# Beacon_V2.net
KiCad netlist of a schematic drawn in Altium Designer
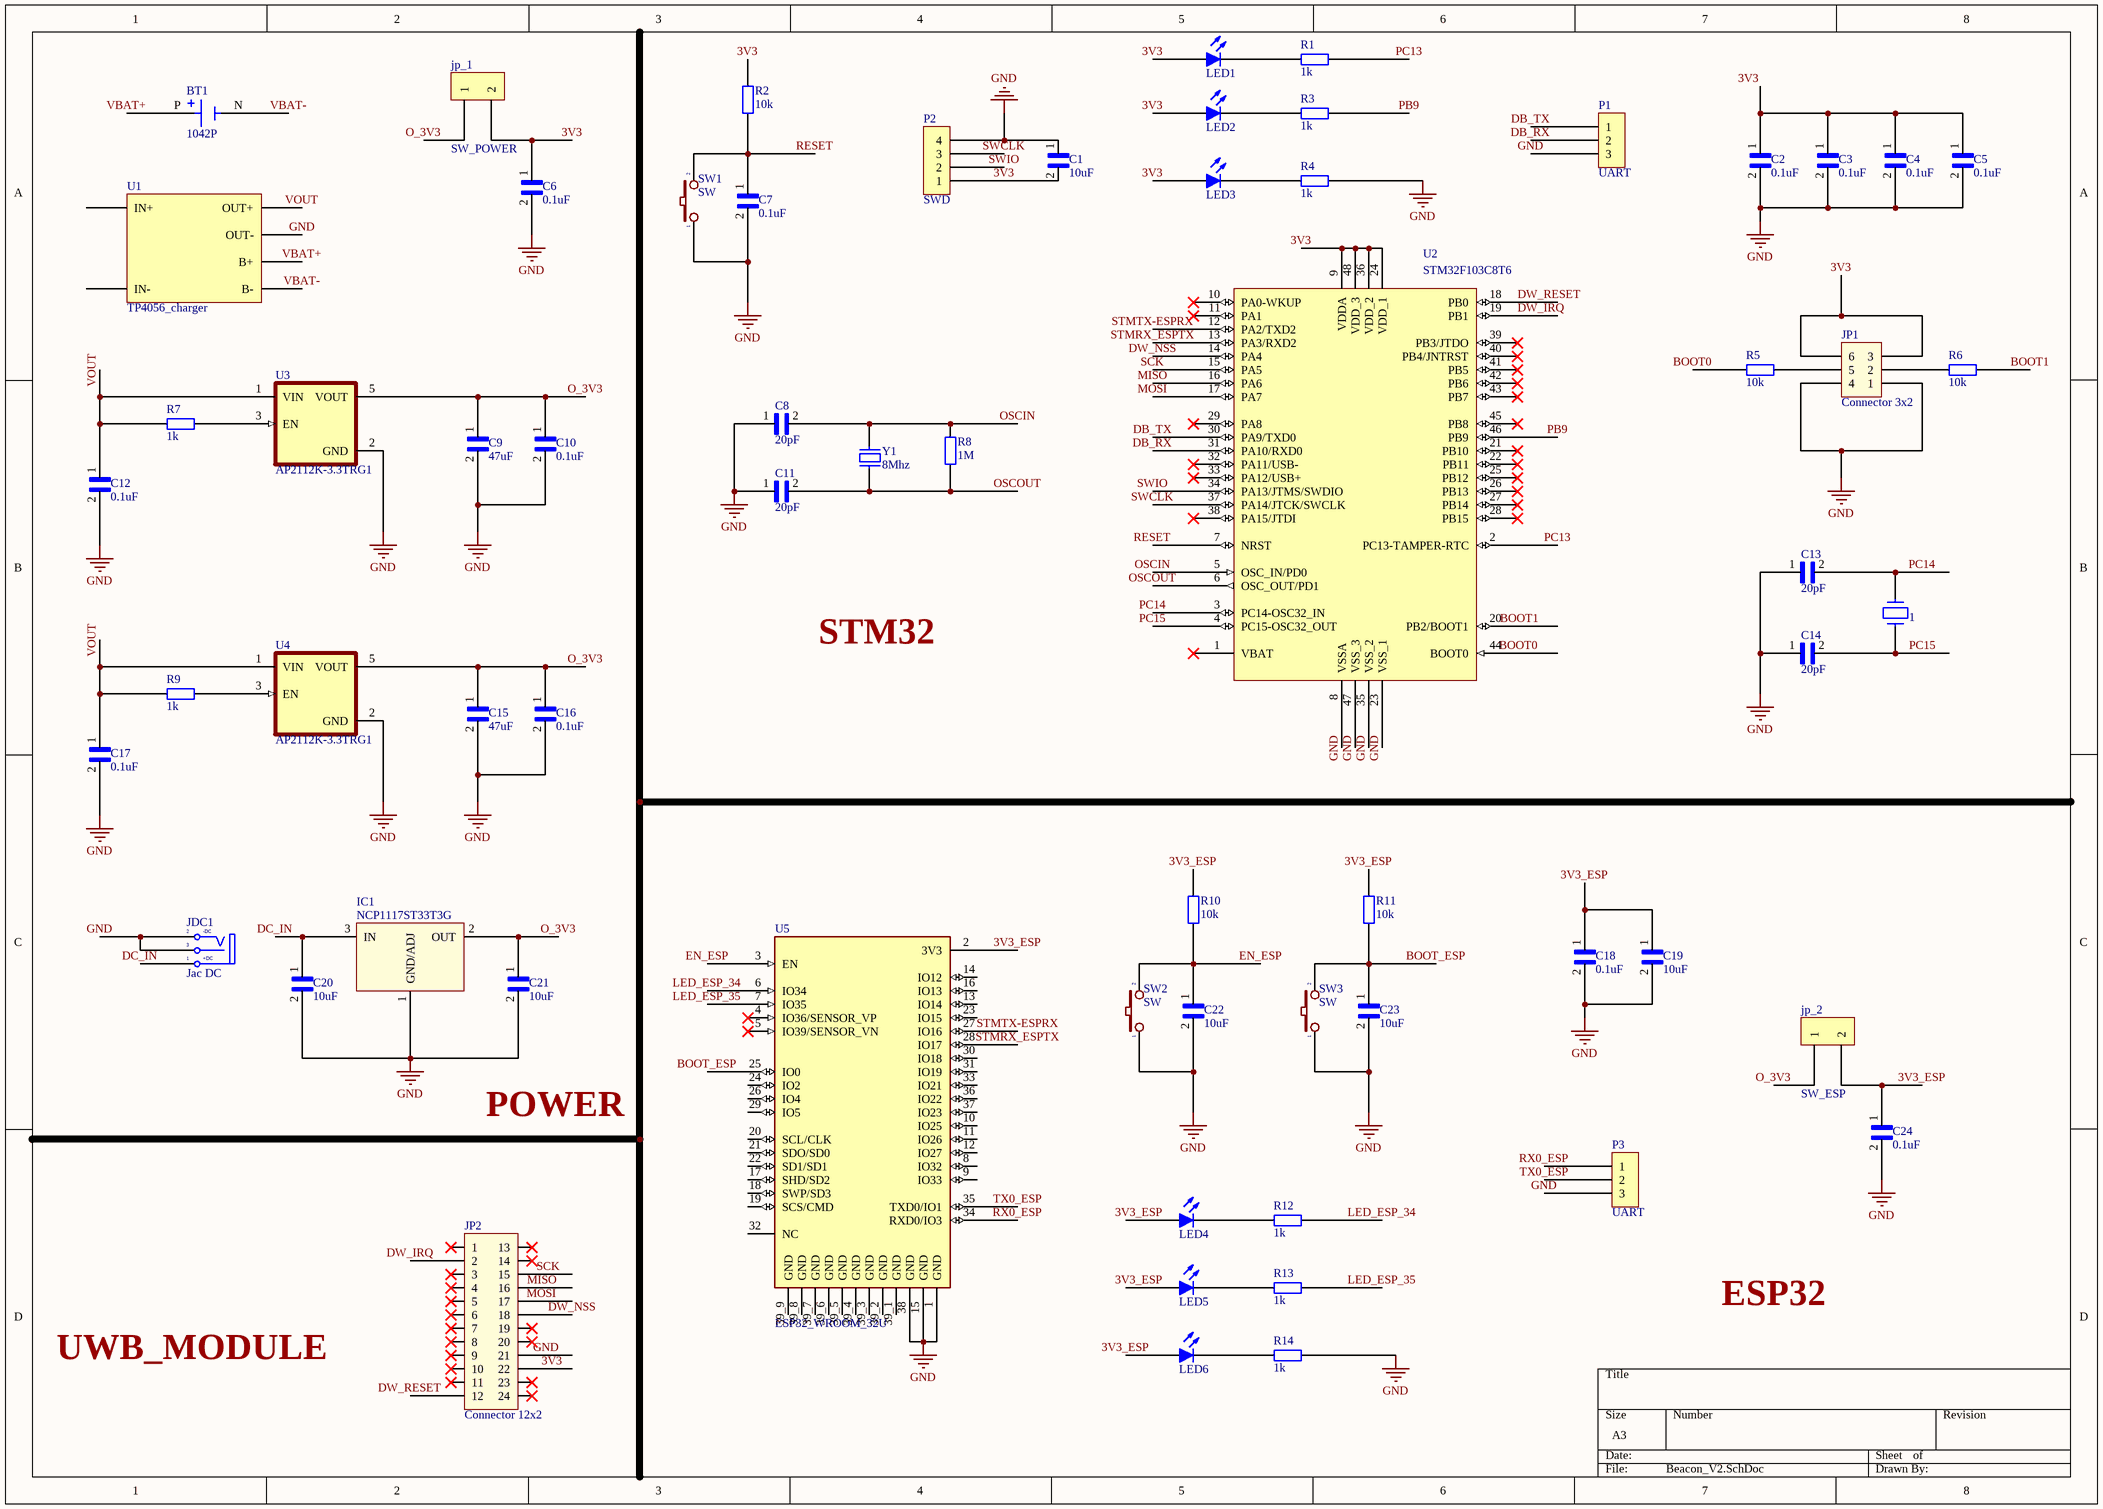
[diagram p0: Beacon_V2.SchDoc]

(export (version "E")
  (design (tool "Eeschema 10.0.6"))
  (components
    (comp (ref "1")
      (value "ABS07")
      (footprint "ABS07")
      (description "SMD Quartz Crystal")
      (fields (field (name "CREATED BY") "Zion Blue") (field (name "PUBLISHER") "Cynetik Group"))
      (libsource (lib "Cty1") (part "ABS07"))
    )
    (comp (ref "BT1")
      (value "1042P")
      (footprint "BAT_1042P")
      (description "SMT Polarized Battery Holder for 18650 Battery ¦ Keystone Electronics 1042P")
      (fields (field (name "MF") "Keystone Electronics"))
      (libsource (lib "Project_LoRa") (part "1042P"))
    )
    (comp (ref "C1")
      (value "10uF")
      (footprint "Capacitor_0805")
      (description "Capacitor; Ceramic; Cap; .220uF; Tol 10%; SMT; Vol-Rtg 50V; X7R; Tape And Reel")
      (libsource (lib "Target_tracking_20242v3") (part "Capacitor_0805"))
    )
    (comp (ref "C2")
      (value "0.1uF")
      (footprint "Capacitor_0805")
      (description "Capacitor; Ceramic; Cap; .220uF; Tol 10%; SMT; Vol-Rtg 50V; X7R; Tape And Reel")
      (libsource (lib "Target_tracking_20242v3") (part "Capacitor_0805"))
    )
    (comp (ref "C3")
      (value "0.1uF")
      (footprint "Capacitor_0805")
      (description "Capacitor; Ceramic; Cap; .220uF; Tol 10%; SMT; Vol-Rtg 50V; X7R; Tape And Reel")
      (libsource (lib "Target_tracking_20242v3") (part "Capacitor_0805"))
    )
    (comp (ref "C4")
      (value "0.1uF")
      (footprint "Capacitor_0805")
      (description "Capacitor; Ceramic; Cap; .220uF; Tol 10%; SMT; Vol-Rtg 50V; X7R; Tape And Reel")
      (libsource (lib "Target_tracking_20242v3") (part "Capacitor_0805"))
    )
    (comp (ref "C5")
      (value "0.1uF")
      (footprint "Capacitor_0805")
      (description "Capacitor; Ceramic; Cap; .220uF; Tol 10%; SMT; Vol-Rtg 50V; X7R; Tape And Reel")
      (libsource (lib "Target_tracking_20242v3") (part "Capacitor_0805"))
    )
    (comp (ref "C6")
      (value "0.1uF")
      (footprint "Capacitor_0805")
      (description "Capacitor; Ceramic; Cap; .220uF; Tol 10%; SMT; Vol-Rtg 50V; X7R; Tape And Reel")
      (libsource (lib "Target_tracking_20242v3") (part "Capacitor_0805"))
    )
    (comp (ref "C7")
      (value "0.1uF")
      (footprint "Capacitor_0805")
      (description "Capacitor; Ceramic; Cap; .220uF; Tol 10%; SMT; Vol-Rtg 50V; X7R; Tape And Reel")
      (libsource (lib "Target_tracking_20242v3") (part "Capacitor_0805"))
    )
    (comp (ref "C8")
      (value "20pF")
      (footprint "Capacitor_0805")
      (description "Capacitor; Ceramic; Cap; .220uF; Tol 10%; SMT; Vol-Rtg 50V; X7R; Tape And Reel")
      (libsource (lib "") (part "Capacitor_0805_1"))
    )
    (comp (ref "C9")
      (value "47uF")
      (footprint "Capacitor_0805")
      (description "Capacitor; Ceramic; Cap; .220uF; Tol 10%; SMT; Vol-Rtg 50V; X7R; Tape And Reel")
      (libsource (lib "Target_tracking_20242v3") (part "Capacitor_0805"))
    )
    (comp (ref "C10")
      (value "0.1uF")
      (footprint "Capacitor_0805")
      (description "Capacitor; Ceramic; Cap; .220uF; Tol 10%; SMT; Vol-Rtg 50V; X7R; Tape And Reel")
      (libsource (lib "Target_tracking_20242v3") (part "Capacitor_0805"))
    )
    (comp (ref "C11")
      (value "20pF")
      (footprint "Capacitor_0805")
      (description "Capacitor; Ceramic; Cap; .220uF; Tol 10%; SMT; Vol-Rtg 50V; X7R; Tape And Reel")
      (libsource (lib "") (part "Capacitor_0805_1"))
    )
    (comp (ref "C12")
      (value "0.1uF")
      (footprint "Capacitor_0805")
      (description "Capacitor; Ceramic; Cap; .220uF; Tol 10%; SMT; Vol-Rtg 50V; X7R; Tape And Reel")
      (libsource (lib "Target_tracking_20242v3") (part "Capacitor_0805"))
    )
    (comp (ref "C13")
      (value "20pF")
      (footprint "Capacitor_0805")
      (description "Capacitor; Ceramic; Cap; .220uF; Tol 10%; SMT; Vol-Rtg 50V; X7R; Tape And Reel")
      (libsource (lib "") (part "Capacitor_0805_1"))
    )
    (comp (ref "C14")
      (value "20pF")
      (footprint "Capacitor_0805")
      (description "Capacitor; Ceramic; Cap; .220uF; Tol 10%; SMT; Vol-Rtg 50V; X7R; Tape And Reel")
      (libsource (lib "") (part "Capacitor_0805_1"))
    )
    (comp (ref "C15")
      (value "47uF")
      (footprint "Capacitor_0805")
      (description "Capacitor; Ceramic; Cap; .220uF; Tol 10%; SMT; Vol-Rtg 50V; X7R; Tape And Reel")
      (libsource (lib "Target_tracking_20242v3") (part "Capacitor_0805"))
    )
    (comp (ref "C16")
      (value "0.1uF")
      (footprint "Capacitor_0805")
      (description "Capacitor; Ceramic; Cap; .220uF; Tol 10%; SMT; Vol-Rtg 50V; X7R; Tape And Reel")
      (libsource (lib "Target_tracking_20242v3") (part "Capacitor_0805"))
    )
    (comp (ref "C17")
      (value "0.1uF")
      (footprint "Capacitor_0805")
      (description "Capacitor; Ceramic; Cap; .220uF; Tol 10%; SMT; Vol-Rtg 50V; X7R; Tape And Reel")
      (libsource (lib "Target_tracking_20242v3") (part "Capacitor_0805"))
    )
    (comp (ref "C18")
      (value "0.1uF")
      (footprint "Capacitor_0805")
      (description "Capacitor; Ceramic; Cap; .220uF; Tol 10%; SMT; Vol-Rtg 50V; X7R; Tape And Reel")
      (libsource (lib "Target_tracking_20242v3") (part "Capacitor_0805"))
    )
    (comp (ref "C19")
      (value "10uF")
      (footprint "Capacitor_0805")
      (description "Capacitor; Ceramic; Cap; .220uF; Tol 10%; SMT; Vol-Rtg 50V; X7R; Tape And Reel")
      (libsource (lib "Target_tracking_20242v3") (part "Capacitor_0805"))
    )
    (comp (ref "C20")
      (value "10uF")
      (footprint "Capacitor_0805")
      (description "Capacitor; Ceramic; Cap; .220uF; Tol 10%; SMT; Vol-Rtg 50V; X7R; Tape And Reel")
      (libsource (lib "Target_tracking_20242v3") (part "Capacitor_0805"))
    )
    (comp (ref "C21")
      (value "10uF")
      (footprint "Capacitor_0805")
      (description "Capacitor; Ceramic; Cap; .220uF; Tol 10%; SMT; Vol-Rtg 50V; X7R; Tape And Reel")
      (libsource (lib "Target_tracking_20242v3") (part "Capacitor_0805"))
    )
    (comp (ref "C22")
      (value "10uF")
      (footprint "Capacitor_0805")
      (description "Capacitor; Ceramic; Cap; .220uF; Tol 10%; SMT; Vol-Rtg 50V; X7R; Tape And Reel")
      (libsource (lib "Target_tracking_20242v3") (part "Capacitor_0805"))
    )
    (comp (ref "C23")
      (value "10uF")
      (footprint "Capacitor_0805")
      (description "Capacitor; Ceramic; Cap; .220uF; Tol 10%; SMT; Vol-Rtg 50V; X7R; Tape And Reel")
      (libsource (lib "Target_tracking_20242v3") (part "Capacitor_0805"))
    )
    (comp (ref "C24")
      (value "0.1uF")
      (footprint "Capacitor_0805")
      (description "Capacitor; Ceramic; Cap; .220uF; Tol 10%; SMT; Vol-Rtg 50V; X7R; Tape And Reel")
      (libsource (lib "Target_tracking_20242v3") (part "Capacitor_0805"))
    )
    (comp (ref "IC1")
      (value "NCP1117ST33T3G")
      (footprint "SOT223-3_ONS")
      (description "SOT223")
      (libsource (lib "SCH_MyLib_0") (part "NCP1117ST33T3G"))
    )
    (comp (ref "JDC1")
      (value "Jac DC")
      (footprint "DC-IN")
      (description "Jac DC input")
      (libsource (lib "syhaunguyen") (part "DCIN"))
    )
    (comp (ref "JP1") (value "Connector 3x2") (footprint "JP3x2") (libsource (lib "Cty1") (part "JP3x2")))
    (comp (ref "JP2")
      (value "Connector 12x2")
      (footprint "JP12X2_1")
      (libsource (lib "Cty1") (part "JP12x2"))
    )
    (comp (ref "jp_1")
      (value "SW_POWER")
      (footprint "JP_1x2")
      (libsource (lib "Target_tracking_20242v3") (part "JP_1x2"))
    )
    (comp (ref "jp_2")
      (value "SW_ESP")
      (footprint "JP_1x2")
      (libsource (lib "Target_tracking_20242v3") (part "JP_1x2"))
    )
    (comp (ref "LED1")
      (value "Led")
      (footprint "Led 0805 Blue")
      (description "Typical LED")
      (libsource (lib "Project_LoRa") (part "Led"))
    )
    (comp (ref "LED2")
      (value "Led")
      (footprint "Led 0805 Blue")
      (description "Typical LED")
      (libsource (lib "Project_LoRa") (part "Led"))
    )
    (comp (ref "LED3")
      (value "Led")
      (footprint "Led 0805 Blue")
      (description "Typical LED")
      (libsource (lib "Project_LoRa") (part "Led"))
    )
    (comp (ref "LED4")
      (value "Led")
      (footprint "Led 0805 Blue")
      (description "Typical LED")
      (libsource (lib "Project_LoRa") (part "Led"))
    )
    (comp (ref "LED5")
      (value "Led")
      (footprint "Led 0805 Blue")
      (description "Typical LED")
      (libsource (lib "Project_LoRa") (part "Led"))
    )
    (comp (ref "LED6")
      (value "Led")
      (footprint "Led 0805 Blue")
      (description "Typical LED")
      (libsource (lib "Project_LoRa") (part "Led"))
    )
    (comp (ref "P1")
      (value "UART")
      (footprint "HDR/Header/3/BOX")
      (description "Header, 3-Pin")
      (libsource (lib "Project_LoRa") (part "Header 3"))
    )
    (comp (ref "P2")
      (value "SWD")
      (footprint "HDR/Header/4/BOX")
      (description "Header, 4-Pin")
      (libsource (lib "Project_LoRa") (part "Header 4_1"))
    )
    (comp (ref "P3")
      (value "UART")
      (footprint "HDR/Header/3/BOX")
      (description "Header, 3-Pin")
      (libsource (lib "Project_LoRa") (part "Header 3"))
    )
    (comp (ref "R1")
      (value "1k")
      (footprint "tro smd 0805")
      (description "Dán")
      (libsource (lib "Project_LoRa") (part "Tro 0805 1% 1k"))
    )
    (comp (ref "R2")
      (value "10k")
      (footprint "tro smd 0805")
      (description "Dán")
      (libsource (lib "Project_LoRa") (part "Tro 0805 1% 10k"))
    )
    (comp (ref "R3")
      (value "1k")
      (footprint "tro smd 0805")
      (description "Dán")
      (libsource (lib "Project_LoRa") (part "Tro 0805 1% 1k"))
    )
    (comp (ref "R4")
      (value "1k")
      (footprint "tro smd 0805")
      (description "Dán")
      (libsource (lib "Project_LoRa") (part "Tro 0805 1% 1k"))
    )
    (comp (ref "R5")
      (value "10k")
      (footprint "tro smd 0805")
      (description "Dán")
      (libsource (lib "Project_LoRa") (part "Tro 0805 1% 10k"))
    )
    (comp (ref "R6")
      (value "10k")
      (footprint "tro smd 0805")
      (description "Dán")
      (libsource (lib "Project_LoRa") (part "Tro 0805 1% 10k"))
    )
    (comp (ref "R7")
      (value "1k")
      (footprint "tro smd 0805")
      (description "Dán")
      (libsource (lib "Project_LoRa") (part "Tro 0805 1% 1k"))
    )
    (comp (ref "R8")
      (value "1M")
      (footprint "tro smd 0805")
      (description "Dán")
      (libsource (lib "Project_LoRa") (part "Tro 0805 1% 1M"))
    )
    (comp (ref "R9")
      (value "1k")
      (footprint "tro smd 0805")
      (description "Dán")
      (libsource (lib "Project_LoRa") (part "Tro 0805 1% 1k"))
    )
    (comp (ref "R10")
      (value "10k")
      (footprint "tro smd 0805")
      (description "Dán")
      (libsource (lib "Project_LoRa") (part "Tro 0805 1% 10k"))
    )
    (comp (ref "R11")
      (value "10k")
      (footprint "tro smd 0805")
      (description "Dán")
      (libsource (lib "Project_LoRa") (part "Tro 0805 1% 10k"))
    )
    (comp (ref "R12")
      (value "1k")
      (footprint "tro smd 0805")
      (description "Dán")
      (libsource (lib "Project_LoRa") (part "Tro 0805 1% 1k"))
    )
    (comp (ref "R13")
      (value "1k")
      (footprint "tro smd 0805")
      (description "Dán")
      (libsource (lib "Project_LoRa") (part "Tro 0805 1% 1k"))
    )
    (comp (ref "R14")
      (value "1k")
      (footprint "tro smd 0805")
      (description "Dán")
      (libsource (lib "Project_LoRa") (part "Tro 0805 1% 1k"))
    )
    (comp (ref "SW1")
      (value "SW")
      (footprint "SW1-SMD")
      (description "Switch button 2 pin")
      (libsource (lib "Project_LoRa") (part "SW2"))
    )
    (comp (ref "SW2")
      (value "SW")
      (footprint "SW1-SMD")
      (description "Switch button 2 pin")
      (libsource (lib "Project_LoRa") (part "SW2"))
    )
    (comp (ref "SW3")
      (value "SW")
      (footprint "SW1-SMD")
      (description "Switch button 2 pin")
      (libsource (lib "Project_LoRa") (part "SW2"))
    )
    (comp (ref "U1")
      (value "TP4056_charger")
      (footprint "TP4056_charger")
      (libsource (lib "Target_tracking_20242v3") (part "TP4056_charger"))
    )
    (comp (ref "U2")
      (value "STM32F103C8T6")
      (footprint "LQFP48")
      (fields (field (name "PUBLISHER") "Altium Limited"))
      (libsource (lib "Project_LoRa") (part "STM32F103C8T6"))
    )
    (comp (ref "U3")
      (value "AP2112K-3.3TRG1")
      (footprint "SOT95P285X140-5N")
      (description "Linear Voltage Regulator IC Positive Fixed 1 Output 600mA SOT-25")
      (fields (field (name "MF") "Diodes Inc."))
      (libsource (lib "Project_LoRa") (part "AP2112K-3.3TRG1"))
    )
    (comp (ref "U4")
      (value "AP2112K-3.3TRG1")
      (footprint "SOT95P285X140-5N")
      (description "Linear Voltage Regulator IC Positive Fixed 1 Output 600mA SOT-25")
      (fields (field (name "MF") "Diodes Inc."))
      (libsource (lib "Project_LoRa") (part "AP2112K-3.3TRG1"))
    )
    (comp (ref "U5")
      (value "ESP32_WROOM_32U")
      (footprint "ESP32_WROOM_32U")
      (libsource (lib "Target_tracking_20242v3") (part "ESP32_WROOM_32U"))
    )
    (comp (ref "Y1")
      (value "8Mhz")
      (footprint "Thach Anh 2 chan SMD5032")
      (description "Crystal For all Crystal 2pin.")
      (libsource (lib "Project_LoRa") (part "Thach Anh 2 chan SMD 5032"))
    )
  )
  (nets
    (net (code "1") (name "/3V3") (class "Default")
      (node (ref "C1") (pin "2") (pinfunction "2_2") (pintype "passive"))
      (node (ref "C2") (pin "1") (pinfunction "1_1") (pintype "passive"))
      (node (ref "C3") (pin "1") (pinfunction "1_1") (pintype "passive"))
      (node (ref "C4") (pin "1") (pinfunction "1_1") (pintype "passive"))
      (node (ref "C5") (pin "1") (pinfunction "1_1") (pintype "passive"))
      (node (ref "C6") (pin "1") (pinfunction "1_1") (pintype "passive"))
      (node (ref "JP1") (pin "3") (pinfunction "3_3") (pintype "passive"))
      (node (ref "JP1") (pin "6") (pinfunction "6_6") (pintype "passive"))
      (node (ref "JP2") (pin "22") (pinfunction "22_22") (pintype "passive"))
      (node (ref "LED1") (pin "1") (pinfunction "A_1") (pintype "passive"))
      (node (ref "LED2") (pin "1") (pinfunction "A_1") (pintype "passive"))
      (node (ref "LED3") (pin "1") (pinfunction "A_1") (pintype "passive"))
      (node (ref "P2") (pin "1") (pinfunction "1_1") (pintype "passive"))
      (node (ref "R2") (pin "2") (pinfunction "2_2") (pintype "passive"))
      (node (ref "U2") (pin "24") (pinfunction "VDD_1_24") (pintype "power_in"))
      (node (ref "U2") (pin "36") (pinfunction "VDD_2_36") (pintype "power_in"))
      (node (ref "U2") (pin "48") (pinfunction "VDD_3_48") (pintype "power_in"))
      (node (ref "U2") (pin "9") (pinfunction "VDDA_9") (pintype "power_in"))
      (node (ref "jp_1") (pin "2") (pinfunction "2_2") (pintype "passive"))
    )
    (net (code "2") (name "/3V3_ESP") (class "Default")
      (node (ref "C18") (pin "1") (pinfunction "1_1") (pintype "passive"))
      (node (ref "C19") (pin "1") (pinfunction "1_1") (pintype "passive"))
      (node (ref "C24") (pin "1") (pinfunction "1_1") (pintype "passive"))
      (node (ref "LED4") (pin "1") (pinfunction "A_1") (pintype "passive"))
      (node (ref "LED5") (pin "1") (pinfunction "A_1") (pintype "passive"))
      (node (ref "LED6") (pin "1") (pinfunction "A_1") (pintype "passive"))
      (node (ref "R10") (pin "2") (pinfunction "2_2") (pintype "passive"))
      (node (ref "R11") (pin "2") (pinfunction "2_2") (pintype "passive"))
      (node (ref "U5") (pin "2") (pinfunction "3V3_2") (pintype "power_in"))
      (node (ref "jp_2") (pin "2") (pinfunction "2_2") (pintype "passive"))
    )
    (net (code "3") (name "/BOOT0") (class "Default")
      (node (ref "R5") (pin "1") (pinfunction "1_1") (pintype "passive"))
      (node (ref "U2") (pin "44") (pinfunction "BOOT0_44") (pintype "input"))
    )
    (net (code "4") (name "/BOOT1") (class "Default")
      (node (ref "R6") (pin "2") (pinfunction "2_2") (pintype "passive"))
      (node (ref "U2") (pin "20") (pinfunction "PB2/BOOT1_20") (pintype "bidirectional"))
    )
    (net (code "5") (name "/BOOT_ESP") (class "Default")
      (node (ref "C23") (pin "1") (pinfunction "1_1") (pintype "passive"))
      (node (ref "R11") (pin "1") (pinfunction "1_1") (pintype "passive"))
      (node (ref "SW3") (pin "2") (pinfunction "2_2") (pintype "passive"))
      (node (ref "U5") (pin "25") (pinfunction "IO0_25") (pintype "bidirectional"))
    )
    (net (code "6") (name "/DB_RX") (class "Default")
      (node (ref "P1") (pin "2") (pinfunction "2_2") (pintype "passive"))
      (node (ref "U2") (pin "31") (pinfunction "PA10/RXD0_31") (pintype "bidirectional"))
    )
    (net (code "7") (name "/DB_TX") (class "Default")
      (node (ref "P1") (pin "1") (pinfunction "1_1") (pintype "passive"))
      (node (ref "U2") (pin "30") (pinfunction "PA9/TXD0_30") (pintype "bidirectional"))
    )
    (net (code "8") (name "/DC_IN") (class "Default")
      (node (ref "C20") (pin "1") (pinfunction "1_1") (pintype "passive"))
      (node (ref "IC1") (pin "3") (pinfunction "IN_3") (pintype "passive"))
      (node (ref "JDC1") (pin "1") (pinfunction "T_1") (pintype "passive"))
    )
    (net (code "9") (name "/DW_IRQ") (class "Default")
      (node (ref "JP2") (pin "2") (pinfunction "2_2") (pintype "passive"))
      (node (ref "U2") (pin "19") (pinfunction "PB1_19") (pintype "bidirectional"))
    )
    (net (code "10") (name "/DW_NSS") (class "Default")
      (node (ref "JP2") (pin "18") (pinfunction "18_18") (pintype "passive"))
      (node (ref "U2") (pin "14") (pinfunction "PA4_14") (pintype "bidirectional"))
    )
    (net (code "11") (name "/DW_RESET") (class "Default")
      (node (ref "JP2") (pin "12") (pinfunction "12_12") (pintype "passive"))
      (node (ref "U2") (pin "18") (pinfunction "PB0_18") (pintype "bidirectional"))
    )
    (net (code "12") (name "/EN_ESP") (class "Default")
      (node (ref "C22") (pin "1") (pinfunction "1_1") (pintype "passive"))
      (node (ref "R10") (pin "1") (pinfunction "1_1") (pintype "passive"))
      (node (ref "SW2") (pin "2") (pinfunction "2_2") (pintype "passive"))
      (node (ref "U5") (pin "3") (pinfunction "EN_3") (pintype "input"))
    )
    (net (code "13") (name "/LED_ESP_34") (class "Default")
      (node (ref "R12") (pin "2") (pinfunction "2_2") (pintype "passive"))
      (node (ref "U5") (pin "6") (pinfunction "IO34_6") (pintype "input"))
    )
    (net (code "14") (name "/LED_ESP_35") (class "Default")
      (node (ref "R13") (pin "2") (pinfunction "2_2") (pintype "passive"))
      (node (ref "U5") (pin "7") (pinfunction "IO35_7") (pintype "input"))
    )
    (net (code "15") (name "/MISO") (class "Default")
      (node (ref "JP2") (pin "16") (pinfunction "16_16") (pintype "passive"))
      (node (ref "U2") (pin "16") (pinfunction "PA6_16") (pintype "bidirectional"))
    )
    (net (code "16") (name "/MOSI") (class "Default")
      (node (ref "JP2") (pin "17") (pinfunction "17_17") (pintype "passive"))
      (node (ref "U2") (pin "17") (pinfunction "PA7_17") (pintype "bidirectional"))
    )
    (net (code "17") (name "/OSCIN") (class "Default")
      (node (ref "C8") (pin "2") (pinfunction "2_2") (pintype "passive"))
      (node (ref "R8") (pin "2") (pinfunction "2_2") (pintype "passive"))
      (node (ref "U2") (pin "5") (pinfunction "OSC_IN/PD0_5") (pintype "input"))
      (node (ref "Y1") (pin "2") (pinfunction "2_2") (pintype "passive"))
    )
    (net (code "18") (name "/OSCOUT") (class "Default")
      (node (ref "C11") (pin "2") (pinfunction "2_2") (pintype "passive"))
      (node (ref "R8") (pin "1") (pinfunction "1_1") (pintype "passive"))
      (node (ref "U2") (pin "6") (pinfunction "OSC_OUT/PD1_6") (pintype "output"))
      (node (ref "Y1") (pin "1") (pinfunction "1_1") (pintype "passive"))
    )
    (net (code "19") (name "/O_3V3") (class "Default")
      (node (ref "C10") (pin "1") (pinfunction "1_1") (pintype "passive"))
      (node (ref "C15") (pin "1") (pinfunction "1_1") (pintype "passive"))
      (node (ref "C16") (pin "1") (pinfunction "1_1") (pintype "passive"))
      (node (ref "C21") (pin "1") (pinfunction "1_1") (pintype "passive"))
      (node (ref "C9") (pin "1") (pinfunction "1_1") (pintype "passive"))
      (node (ref "IC1") (pin "2") (pinfunction "OUT_2") (pintype "passive"))
      (node (ref "U3") (pin "5") (pinfunction "VOUT_5") (pintype "power_in"))
      (node (ref "U4") (pin "5") (pinfunction "VOUT_5") (pintype "power_in"))
      (node (ref "jp_1") (pin "1") (pinfunction "1_1") (pintype "passive"))
      (node (ref "jp_2") (pin "1") (pinfunction "1_1") (pintype "passive"))
    )
    (net (code "20") (name "/PB9") (class "Default")
      (node (ref "R3") (pin "2") (pinfunction "2_2") (pintype "passive"))
      (node (ref "U2") (pin "46") (pinfunction "PB9_46") (pintype "bidirectional"))
    )
    (net (code "21") (name "/PC13") (class "Default")
      (node (ref "R1") (pin "2") (pinfunction "2_2") (pintype "passive"))
      (node (ref "U2") (pin "2") (pinfunction "PC13-TAMPER-RTC_2") (pintype "bidirectional"))
    )
    (net (code "22") (name "/PC14") (class "Default")
      (node (ref "1") (pin "2") (pinfunction "2_2") (pintype "passive"))
      (node (ref "C13") (pin "2") (pinfunction "2_2") (pintype "passive"))
      (node (ref "U2") (pin "3") (pinfunction "PC14-OSC32_IN_3") (pintype "bidirectional"))
    )
    (net (code "23") (name "/PC15") (class "Default")
      (node (ref "1") (pin "1") (pinfunction "1_1") (pintype "passive"))
      (node (ref "C14") (pin "2") (pinfunction "2_2") (pintype "passive"))
      (node (ref "U2") (pin "4") (pinfunction "PC15-OSC32_OUT_4") (pintype "bidirectional"))
    )
    (net (code "24") (name "/RESET") (class "Default")
      (node (ref "C7") (pin "1") (pinfunction "1_1") (pintype "passive"))
      (node (ref "R2") (pin "1") (pinfunction "1_1") (pintype "passive"))
      (node (ref "SW1") (pin "2") (pinfunction "2_2") (pintype "passive"))
      (node (ref "U2") (pin "7") (pinfunction "NRST_7") (pintype "bidirectional"))
    )
    (net (code "25") (name "/RX0_ESP") (class "Default")
      (node (ref "P3") (pin "1") (pinfunction "1_1") (pintype "passive"))
      (node (ref "U5") (pin "34") (pinfunction "RXD0/IO3_34") (pintype "bidirectional"))
    )
    (net (code "26") (name "/SCK") (class "Default")
      (node (ref "JP2") (pin "15") (pinfunction "15_15") (pintype "passive"))
      (node (ref "U2") (pin "15") (pinfunction "PA5_15") (pintype "bidirectional"))
    )
    (net (code "27") (name "/STMRX_ESPTX") (class "Default")
      (node (ref "U2") (pin "13") (pinfunction "PA3/RXD2_13") (pintype "bidirectional"))
      (node (ref "U5") (pin "28") (pinfunction "IO17_28") (pintype "bidirectional"))
    )
    (net (code "28") (name "/STMTX-ESPRX") (class "Default")
      (node (ref "U2") (pin "12") (pinfunction "PA2/TXD2_12") (pintype "bidirectional"))
      (node (ref "U5") (pin "27") (pinfunction "IO16_27") (pintype "bidirectional"))
    )
    (net (code "29") (name "/SWCLK") (class "Default")
      (node (ref "P2") (pin "3") (pinfunction "3_3") (pintype "passive"))
      (node (ref "U2") (pin "37") (pinfunction "PA14/JTCK/SWCLK_37") (pintype "bidirectional"))
    )
    (net (code "30") (name "/SWIO") (class "Default")
      (node (ref "P2") (pin "2") (pinfunction "2_2") (pintype "passive"))
      (node (ref "U2") (pin "34") (pinfunction "PA13/JTMS/SWDIO_34") (pintype "bidirectional"))
    )
    (net (code "31") (name "/TX0_ESP") (class "Default")
      (node (ref "P3") (pin "2") (pinfunction "2_2") (pintype "passive"))
      (node (ref "U5") (pin "35") (pinfunction "TXD0/IO1_35") (pintype "bidirectional"))
    )
    (net (code "32") (name "/VBAT+") (class "Default")
      (node (ref "BT1") (pin "P") (pinfunction "POS_P") (pintype "passive"))
      (node (ref "U1") (pin "1") (pinfunction "B+_1") (pintype "passive"))
    )
    (net (code "33") (name "/VBAT-") (class "Default")
      (node (ref "BT1") (pin "N") (pinfunction "NEG_N") (pintype "passive"))
      (node (ref "U1") (pin "2") (pinfunction "B-_2") (pintype "passive"))
    )
    (net (code "34") (name "/VOUT") (class "Default")
      (node (ref "C12") (pin "1") (pinfunction "1_1") (pintype "passive"))
      (node (ref "C17") (pin "1") (pinfunction "1_1") (pintype "passive"))
      (node (ref "R7") (pin "1") (pinfunction "1_1") (pintype "passive"))
      (node (ref "R9") (pin "1") (pinfunction "1_1") (pintype "passive"))
      (node (ref "U1") (pin "3") (pinfunction "OUT+_3") (pintype "passive"))
      (node (ref "U3") (pin "1") (pinfunction "VIN_1") (pintype "power_in"))
      (node (ref "U4") (pin "1") (pinfunction "VIN_1") (pintype "power_in"))
    )
    (net (code "35") (name "GND") (class "Default")
      (node (ref "C1") (pin "1") (pinfunction "1_1") (pintype "passive"))
      (node (ref "C10") (pin "2") (pinfunction "2_2") (pintype "passive"))
      (node (ref "C11") (pin "1") (pinfunction "1_1") (pintype "passive"))
      (node (ref "C12") (pin "2") (pinfunction "2_2") (pintype "passive"))
      (node (ref "C13") (pin "1") (pinfunction "1_1") (pintype "passive"))
      (node (ref "C14") (pin "1") (pinfunction "1_1") (pintype "passive"))
      (node (ref "C15") (pin "2") (pinfunction "2_2") (pintype "passive"))
      (node (ref "C16") (pin "2") (pinfunction "2_2") (pintype "passive"))
      (node (ref "C17") (pin "2") (pinfunction "2_2") (pintype "passive"))
      (node (ref "C18") (pin "2") (pinfunction "2_2") (pintype "passive"))
      (node (ref "C19") (pin "2") (pinfunction "2_2") (pintype "passive"))
      (node (ref "C2") (pin "2") (pinfunction "2_2") (pintype "passive"))
      (node (ref "C20") (pin "2") (pinfunction "2_2") (pintype "passive"))
      (node (ref "C21") (pin "2") (pinfunction "2_2") (pintype "passive"))
      (node (ref "C22") (pin "2") (pinfunction "2_2") (pintype "passive"))
      (node (ref "C23") (pin "2") (pinfunction "2_2") (pintype "passive"))
      (node (ref "C24") (pin "2") (pinfunction "2_2") (pintype "passive"))
      (node (ref "C3") (pin "2") (pinfunction "2_2") (pintype "passive"))
      (node (ref "C4") (pin "2") (pinfunction "2_2") (pintype "passive"))
      (node (ref "C5") (pin "2") (pinfunction "2_2") (pintype "passive"))
      (node (ref "C6") (pin "2") (pinfunction "2_2") (pintype "passive"))
      (node (ref "C7") (pin "2") (pinfunction "2_2") (pintype "passive"))
      (node (ref "C8") (pin "1") (pinfunction "1_1") (pintype "passive"))
      (node (ref "C9") (pin "2") (pinfunction "2_2") (pintype "passive"))
      (node (ref "IC1") (pin "1") (pinfunction "GND/ADJ_1") (pintype "passive"))
      (node (ref "JDC1") (pin "2") (pinfunction "TN_2") (pintype "passive"))
      (node (ref "JDC1") (pin "3") (pinfunction "S_3") (pintype "power_in"))
      (node (ref "JP1") (pin "1") (pinfunction "1_1") (pintype "passive"))
      (node (ref "JP1") (pin "4") (pinfunction "4_4") (pintype "passive"))
      (node (ref "JP2") (pin "21") (pinfunction "21_21") (pintype "passive"))
      (node (ref "P1") (pin "3") (pinfunction "3_3") (pintype "passive"))
      (node (ref "P2") (pin "4") (pinfunction "4_4") (pintype "passive"))
      (node (ref "P3") (pin "3") (pinfunction "3_3") (pintype "passive"))
      (node (ref "R14") (pin "2") (pinfunction "2_2") (pintype "passive"))
      (node (ref "R4") (pin "2") (pinfunction "2_2") (pintype "passive"))
      (node (ref "SW1") (pin "1") (pinfunction "1_1") (pintype "passive"))
      (node (ref "SW2") (pin "1") (pinfunction "1_1") (pintype "passive"))
      (node (ref "SW3") (pin "1") (pinfunction "1_1") (pintype "passive"))
      (node (ref "U1") (pin "4") (pinfunction "OUT-_4") (pintype "passive"))
      (node (ref "U2") (pin "23") (pinfunction "VSS_1_23") (pintype "power_in"))
      (node (ref "U2") (pin "35") (pinfunction "VSS_2_35") (pintype "power_in"))
      (node (ref "U2") (pin "47") (pinfunction "VSS_3_47") (pintype "power_in"))
      (node (ref "U2") (pin "8") (pinfunction "VSSA_8") (pintype "power_in"))
      (node (ref "U3") (pin "2") (pinfunction "GND_2") (pintype "power_in"))
      (node (ref "U4") (pin "2") (pinfunction "GND_2") (pintype "power_in"))
      (node (ref "U5") (pin "1") (pinfunction "GND_1") (pintype "power_in"))
      (node (ref "U5") (pin "15") (pinfunction "GND_15") (pintype "power_in"))
      (node (ref "U5") (pin "38") (pinfunction "GND_38") (pintype "power_in"))
    )
    (net (code "36") (name "Net-(JP1-Pad2)") (class "Default")
      (node (ref "JP1") (pin "2") (pinfunction "2_2") (pintype "passive"))
      (node (ref "R6") (pin "1") (pinfunction "1_1") (pintype "passive"))
    )
    (net (code "37") (name "Net-(JP1-Pad5)") (class "Default")
      (node (ref "JP1") (pin "5") (pinfunction "5_5") (pintype "passive"))
      (node (ref "R5") (pin "2") (pinfunction "2_2") (pintype "passive"))
    )
    (net (code "38") (name "Net-(LED1-K)") (class "Default")
      (node (ref "LED1") (pin "2") (pinfunction "K_2") (pintype "passive"))
      (node (ref "R1") (pin "1") (pinfunction "1_1") (pintype "passive"))
    )
    (net (code "39") (name "Net-(LED2-K)") (class "Default")
      (node (ref "LED2") (pin "2") (pinfunction "K_2") (pintype "passive"))
      (node (ref "R3") (pin "1") (pinfunction "1_1") (pintype "passive"))
    )
    (net (code "40") (name "Net-(LED3-K)") (class "Default")
      (node (ref "LED3") (pin "2") (pinfunction "K_2") (pintype "passive"))
      (node (ref "R4") (pin "1") (pinfunction "1_1") (pintype "passive"))
    )
    (net (code "41") (name "Net-(LED4-K)") (class "Default")
      (node (ref "LED4") (pin "2") (pinfunction "K_2") (pintype "passive"))
      (node (ref "R12") (pin "1") (pinfunction "1_1") (pintype "passive"))
    )
    (net (code "42") (name "Net-(LED5-K)") (class "Default")
      (node (ref "LED5") (pin "2") (pinfunction "K_2") (pintype "passive"))
      (node (ref "R13") (pin "1") (pinfunction "1_1") (pintype "passive"))
    )
    (net (code "43") (name "Net-(LED6-K)") (class "Default")
      (node (ref "LED6") (pin "2") (pinfunction "K_2") (pintype "passive"))
      (node (ref "R14") (pin "1") (pinfunction "1_1") (pintype "passive"))
    )
    (net (code "44") (name "Net-(U3-EN)") (class "Default")
      (node (ref "R7") (pin "2") (pinfunction "2_2") (pintype "passive"))
      (node (ref "U3") (pin "3") (pinfunction "EN_3") (pintype "input"))
    )
    (net (code "45") (name "Net-(U4-EN)") (class "Default")
      (node (ref "R9") (pin "2") (pinfunction "2_2") (pintype "passive"))
      (node (ref "U4") (pin "3") (pinfunction "EN_3") (pintype "input"))
    )
    (net (code "46") (name "unconnected-(JP2-Pad1)") (class "Default")
      (node (ref "JP2") (pin "1") (pinfunction "1_1") (pintype "passive+no_connect"))
    )
    (net (code "47") (name "unconnected-(JP2-Pad3)") (class "Default")
      (node (ref "JP2") (pin "3") (pinfunction "3_3") (pintype "passive+no_connect"))
    )
    (net (code "48") (name "unconnected-(JP2-Pad4)") (class "Default")
      (node (ref "JP2") (pin "4") (pinfunction "4_4") (pintype "passive+no_connect"))
    )
    (net (code "49") (name "unconnected-(JP2-Pad5)") (class "Default")
      (node (ref "JP2") (pin "5") (pinfunction "5_5") (pintype "passive+no_connect"))
    )
    (net (code "50") (name "unconnected-(JP2-Pad6)") (class "Default")
      (node (ref "JP2") (pin "6") (pinfunction "6_6") (pintype "passive+no_connect"))
    )
    (net (code "51") (name "unconnected-(JP2-Pad7)") (class "Default")
      (node (ref "JP2") (pin "7") (pinfunction "7_7") (pintype "passive+no_connect"))
    )
    (net (code "52") (name "unconnected-(JP2-Pad8)") (class "Default")
      (node (ref "JP2") (pin "8") (pinfunction "8_8") (pintype "passive+no_connect"))
    )
    (net (code "53") (name "unconnected-(JP2-Pad9)") (class "Default")
      (node (ref "JP2") (pin "9") (pinfunction "9_9") (pintype "passive+no_connect"))
    )
    (net (code "54") (name "unconnected-(JP2-Pad10)") (class "Default")
      (node (ref "JP2") (pin "10") (pinfunction "10_10") (pintype "passive+no_connect"))
    )
    (net (code "55") (name "unconnected-(JP2-Pad11)") (class "Default")
      (node (ref "JP2") (pin "11") (pinfunction "11_11") (pintype "passive+no_connect"))
    )
    (net (code "56") (name "unconnected-(JP2-Pad13)") (class "Default")
      (node (ref "JP2") (pin "13") (pinfunction "13_13") (pintype "passive+no_connect"))
    )
    (net (code "57") (name "unconnected-(JP2-Pad14)") (class "Default")
      (node (ref "JP2") (pin "14") (pinfunction "14_14") (pintype "passive+no_connect"))
    )
    (net (code "58") (name "unconnected-(JP2-Pad19)") (class "Default")
      (node (ref "JP2") (pin "19") (pinfunction "19_19") (pintype "passive+no_connect"))
    )
    (net (code "59") (name "unconnected-(JP2-Pad20)") (class "Default")
      (node (ref "JP2") (pin "20") (pinfunction "20_20") (pintype "passive+no_connect"))
    )
    (net (code "60") (name "unconnected-(JP2-Pad23)") (class "Default")
      (node (ref "JP2") (pin "23") (pinfunction "23_23") (pintype "passive+no_connect"))
    )
    (net (code "61") (name "unconnected-(JP2-Pad24)") (class "Default")
      (node (ref "JP2") (pin "24") (pinfunction "24_24") (pintype "passive+no_connect"))
    )
    (net (code "62") (name "unconnected-(U1-IN+-Pad5)") (class "Default")
      (node (ref "U1") (pin "5") (pinfunction "IN+_5") (pintype "passive"))
    )
    (net (code "63") (name "unconnected-(U1-IN--Pad6)") (class "Default")
      (node (ref "U1") (pin "6") (pinfunction "IN-_6") (pintype "passive"))
    )
    (net (code "64") (name "unconnected-(U2-PA0-WKUP-Pad10)") (class "Default")
      (node (ref "U2") (pin "10") (pinfunction "PA0-WKUP_10") (pintype "bidirectional+no_connect"))
    )
    (net (code "65") (name "unconnected-(U2-PA1-Pad11)") (class "Default")
      (node (ref "U2") (pin "11") (pinfunction "PA1_11") (pintype "bidirectional+no_connect"))
    )
    (net (code "66") (name "unconnected-(U2-PA8-Pad29)") (class "Default")
      (node (ref "U2") (pin "29") (pinfunction "PA8_29") (pintype "bidirectional+no_connect"))
    )
    (net (code "67") (name "unconnected-(U2-PA11{slash}USB--Pad32)") (class "Default")
      (node (ref "U2") (pin "32") (pinfunction "PA11/USB-_32") (pintype "bidirectional+no_connect"))
    )
    (net (code "68") (name "unconnected-(U2-PA12{slash}USB+-Pad33)") (class "Default")
      (node (ref "U2") (pin "33") (pinfunction "PA12/USB+_33") (pintype "bidirectional+no_connect"))
    )
    (net (code "69") (name "unconnected-(U2-PA15{slash}JTDI-Pad38)") (class "Default")
      (node (ref "U2") (pin "38") (pinfunction "PA15/JTDI_38") (pintype "bidirectional+no_connect"))
    )
    (net (code "70") (name "unconnected-(U2-PB3{slash}JTDO-Pad39)") (class "Default")
      (node (ref "U2") (pin "39") (pinfunction "PB3/JTDO_39") (pintype "bidirectional+no_connect"))
    )
    (net (code "71") (name "unconnected-(U2-PB4{slash}JNTRST-Pad40)") (class "Default")
      (node (ref "U2") (pin "40") (pinfunction "PB4/JNTRST_40") (pintype "bidirectional+no_connect"))
    )
    (net (code "72") (name "unconnected-(U2-PB5-Pad41)") (class "Default")
      (node (ref "U2") (pin "41") (pinfunction "PB5_41") (pintype "bidirectional+no_connect"))
    )
    (net (code "73") (name "unconnected-(U2-PB6-Pad42)") (class "Default")
      (node (ref "U2") (pin "42") (pinfunction "PB6_42") (pintype "bidirectional+no_connect"))
    )
    (net (code "74") (name "unconnected-(U2-PB7-Pad43)") (class "Default")
      (node (ref "U2") (pin "43") (pinfunction "PB7_43") (pintype "bidirectional+no_connect"))
    )
    (net (code "75") (name "unconnected-(U2-PB8-Pad45)") (class "Default")
      (node (ref "U2") (pin "45") (pinfunction "PB8_45") (pintype "bidirectional+no_connect"))
    )
    (net (code "76") (name "unconnected-(U2-PB10-Pad21)") (class "Default")
      (node (ref "U2") (pin "21") (pinfunction "PB10_21") (pintype "bidirectional+no_connect"))
    )
    (net (code "77") (name "unconnected-(U2-PB11-Pad22)") (class "Default")
      (node (ref "U2") (pin "22") (pinfunction "PB11_22") (pintype "bidirectional+no_connect"))
    )
    (net (code "78") (name "unconnected-(U2-PB12-Pad25)") (class "Default")
      (node (ref "U2") (pin "25") (pinfunction "PB12_25") (pintype "bidirectional+no_connect"))
    )
    (net (code "79") (name "unconnected-(U2-PB13-Pad26)") (class "Default")
      (node (ref "U2") (pin "26") (pinfunction "PB13_26") (pintype "bidirectional+no_connect"))
    )
    (net (code "80") (name "unconnected-(U2-PB14-Pad27)") (class "Default")
      (node (ref "U2") (pin "27") (pinfunction "PB14_27") (pintype "bidirectional+no_connect"))
    )
    (net (code "81") (name "unconnected-(U2-PB15-Pad28)") (class "Default")
      (node (ref "U2") (pin "28") (pinfunction "PB15_28") (pintype "bidirectional+no_connect"))
    )
    (net (code "82") (name "unconnected-(U2-VBAT-Pad1)") (class "Default")
      (node (ref "U2") (pin "1") (pinfunction "VBAT_1") (pintype "power_in+no_connect"))
    )
    (net (code "83") (name "unconnected-(U5-GND-Pad39_1)") (class "Default")
      (node (ref "U5") (pin "39_1") (pinfunction "GND_39_1") (pintype "power_in"))
    )
    (net (code "84") (name "unconnected-(U5-GND-Pad39_2)") (class "Default")
      (node (ref "U5") (pin "39_2") (pinfunction "GND_39_2") (pintype "power_in"))
    )
    (net (code "85") (name "unconnected-(U5-GND-Pad39_3)") (class "Default")
      (node (ref "U5") (pin "39_3") (pinfunction "GND_39_3") (pintype "power_in"))
    )
    (net (code "86") (name "unconnected-(U5-GND-Pad39_4)") (class "Default")
      (node (ref "U5") (pin "39_4") (pinfunction "GND_39_4") (pintype "power_in"))
    )
    (net (code "87") (name "unconnected-(U5-GND-Pad39_5)") (class "Default")
      (node (ref "U5") (pin "39_5") (pinfunction "GND_39_5") (pintype "power_in"))
    )
    (net (code "88") (name "unconnected-(U5-GND-Pad39_6)") (class "Default")
      (node (ref "U5") (pin "39_6") (pinfunction "GND_39_6") (pintype "power_in"))
    )
    (net (code "89") (name "unconnected-(U5-GND-Pad39_7)") (class "Default")
      (node (ref "U5") (pin "39_7") (pinfunction "GND_39_7") (pintype "power_in"))
    )
    (net (code "90") (name "unconnected-(U5-GND-Pad39_8)") (class "Default")
      (node (ref "U5") (pin "39_8") (pinfunction "GND_39_8") (pintype "power_in"))
    )
    (net (code "91") (name "unconnected-(U5-GND-Pad39_9)") (class "Default")
      (node (ref "U5") (pin "39_9") (pinfunction "GND_39_9") (pintype "power_in"))
    )
    (net (code "92") (name "unconnected-(U5-IO2-Pad24)") (class "Default")
      (node (ref "U5") (pin "24") (pinfunction "IO2_24") (pintype "bidirectional"))
    )
    (net (code "93") (name "unconnected-(U5-IO4-Pad26)") (class "Default")
      (node (ref "U5") (pin "26") (pinfunction "IO4_26") (pintype "bidirectional"))
    )
    (net (code "94") (name "unconnected-(U5-IO5-Pad29)") (class "Default")
      (node (ref "U5") (pin "29") (pinfunction "IO5_29") (pintype "bidirectional"))
    )
    (net (code "95") (name "unconnected-(U5-IO12-Pad14)") (class "Default")
      (node (ref "U5") (pin "14") (pinfunction "IO12_14") (pintype "bidirectional"))
    )
    (net (code "96") (name "unconnected-(U5-IO13-Pad16)") (class "Default")
      (node (ref "U5") (pin "16") (pinfunction "IO13_16") (pintype "bidirectional"))
    )
    (net (code "97") (name "unconnected-(U5-IO14-Pad13)") (class "Default")
      (node (ref "U5") (pin "13") (pinfunction "IO14_13") (pintype "bidirectional"))
    )
    (net (code "98") (name "unconnected-(U5-IO15-Pad23)") (class "Default")
      (node (ref "U5") (pin "23") (pinfunction "IO15_23") (pintype "bidirectional"))
    )
    (net (code "99") (name "unconnected-(U5-IO18-Pad30)") (class "Default")
      (node (ref "U5") (pin "30") (pinfunction "IO18_30") (pintype "bidirectional"))
    )
    (net (code "100") (name "unconnected-(U5-IO19-Pad31)") (class "Default")
      (node (ref "U5") (pin "31") (pinfunction "IO19_31") (pintype "bidirectional"))
    )
    (net (code "101") (name "unconnected-(U5-IO21-Pad33)") (class "Default")
      (node (ref "U5") (pin "33") (pinfunction "IO21_33") (pintype "bidirectional"))
    )
    (net (code "102") (name "unconnected-(U5-IO22-Pad36)") (class "Default")
      (node (ref "U5") (pin "36") (pinfunction "IO22_36") (pintype "bidirectional"))
    )
    (net (code "103") (name "unconnected-(U5-IO23-Pad37)") (class "Default")
      (node (ref "U5") (pin "37") (pinfunction "IO23_37") (pintype "bidirectional"))
    )
    (net (code "104") (name "unconnected-(U5-IO25-Pad10)") (class "Default")
      (node (ref "U5") (pin "10") (pinfunction "IO25_10") (pintype "bidirectional"))
    )
    (net (code "105") (name "unconnected-(U5-IO26-Pad11)") (class "Default")
      (node (ref "U5") (pin "11") (pinfunction "IO26_11") (pintype "bidirectional"))
    )
    (net (code "106") (name "unconnected-(U5-IO27-Pad12)") (class "Default")
      (node (ref "U5") (pin "12") (pinfunction "IO27_12") (pintype "bidirectional"))
    )
    (net (code "107") (name "unconnected-(U5-IO32-Pad8)") (class "Default")
      (node (ref "U5") (pin "8") (pinfunction "IO32_8") (pintype "bidirectional"))
    )
    (net (code "108") (name "unconnected-(U5-IO33-Pad9)") (class "Default")
      (node (ref "U5") (pin "9") (pinfunction "IO33_9") (pintype "bidirectional"))
    )
    (net (code "109") (name "unconnected-(U5-IO36{slash}SENSOR_VP-Pad4)") (class "Default")
      (node (ref "U5") (pin "4") (pinfunction "IO36/SENSOR_VP_4") (pintype "input+no_connect"))
    )
    (net (code "110") (name "unconnected-(U5-IO39{slash}SENSOR_VN-Pad5)") (class "Default")
      (node (ref "U5") (pin "5") (pinfunction "IO39/SENSOR_VN_5") (pintype "input+no_connect"))
    )
    (net (code "111") (name "unconnected-(U5-NC-Pad32)") (class "Default")
      (node (ref "U5") (pin "32") (pinfunction "NC_32") (pintype "passive"))
    )
    (net (code "112") (name "unconnected-(U5-SCL{slash}CLK-Pad20)") (class "Default")
      (node (ref "U5") (pin "20") (pinfunction "SCL/CLK_20") (pintype "bidirectional"))
    )
    (net (code "113") (name "unconnected-(U5-SCS{slash}CMD-Pad19)") (class "Default")
      (node (ref "U5") (pin "19") (pinfunction "SCS/CMD_19") (pintype "bidirectional"))
    )
    (net (code "114") (name "unconnected-(U5-SD1{slash}SD1-Pad22)") (class "Default")
      (node (ref "U5") (pin "22") (pinfunction "SD1/SD1_22") (pintype "bidirectional"))
    )
    (net (code "115") (name "unconnected-(U5-SDO{slash}SD0-Pad21)") (class "Default")
      (node (ref "U5") (pin "21") (pinfunction "SDO/SD0_21") (pintype "bidirectional"))
    )
    (net (code "116") (name "unconnected-(U5-SHD{slash}SD2-Pad17)") (class "Default")
      (node (ref "U5") (pin "17") (pinfunction "SHD/SD2_17") (pintype "bidirectional"))
    )
    (net (code "117") (name "unconnected-(U5-SWP{slash}SD3-Pad18)") (class "Default")
      (node (ref "U5") (pin "18") (pinfunction "SWP/SD3_18") (pintype "bidirectional"))
    )
  )
)
